# Classes.net
KiCad netlist of a schematic drawn in Altium Designer
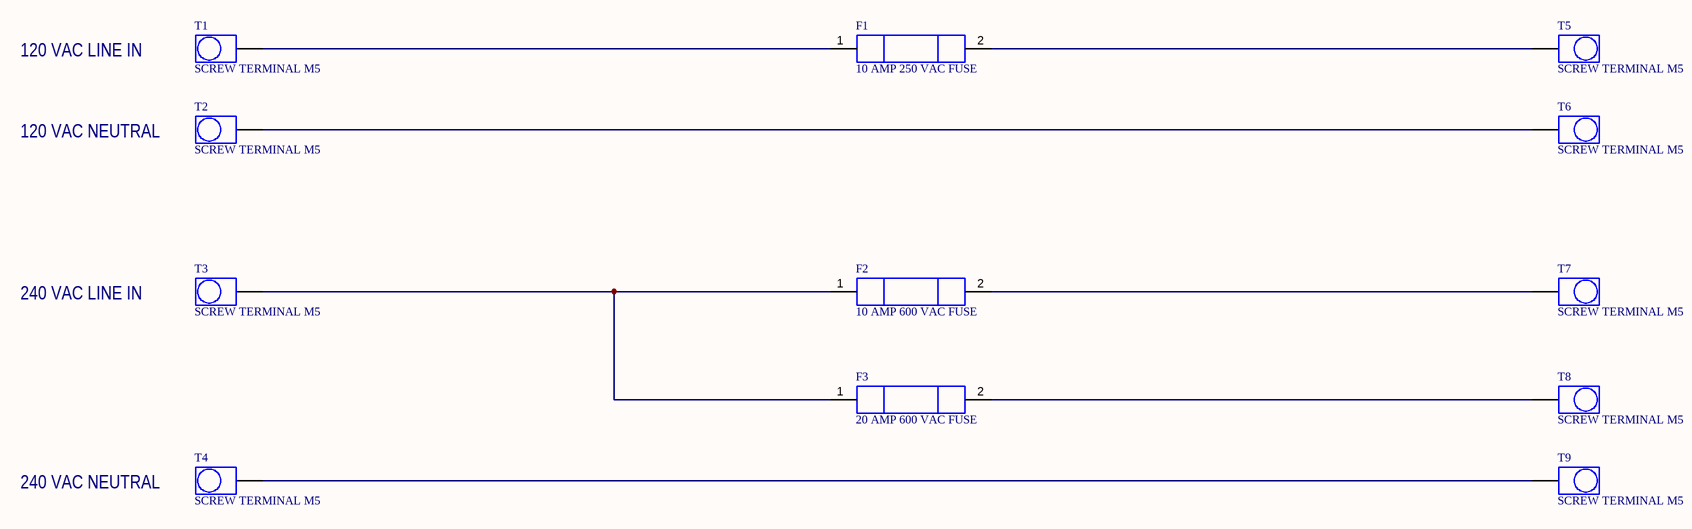
[diagram p0: Classes.SchDoc]

(export (version "E")
  (design (tool "Eeschema 10.0.6"))
  (components
    (comp (ref "F1")
      (value "10 AMP 250 VAC FUSE")
      (footprint "FUSE")
      (libsource (lib "MHH -  Altium Advanced Course A365 01") (part "Fuse3"))
    )
    (comp (ref "F2")
      (value "10 AMP 600 VAC FUSE")
      (footprint "FUSE")
      (libsource (lib "MHH -  Altium Advanced Course A365 01") (part "Fuse3"))
    )
    (comp (ref "F3")
      (value "20 AMP 600 VAC FUSE")
      (footprint "FUSE")
      (libsource (lib "MHH -  Altium Advanced Course A365 01") (part "Fuse3"))
    )
    (comp (ref "T1")
      (value "SCREW TERMINAL M5")
      (footprint "SCREW TERMINAL M5-Footprint")
      (libsource (lib "MHH -  Altium Advanced Course A365 01") (part "SCREW TERMINAL M5"))
    )
    (comp (ref "T2")
      (value "SCREW TERMINAL M5")
      (footprint "SCREW TERMINAL M5-Footprint")
      (libsource (lib "MHH -  Altium Advanced Course A365 01") (part "SCREW TERMINAL M5"))
    )
    (comp (ref "T3")
      (value "SCREW TERMINAL M5")
      (footprint "SCREW TERMINAL M5-Footprint")
      (libsource (lib "MHH -  Altium Advanced Course A365 01") (part "SCREW TERMINAL M5"))
    )
    (comp (ref "T4")
      (value "SCREW TERMINAL M5")
      (footprint "SCREW TERMINAL M5-Footprint")
      (libsource (lib "MHH -  Altium Advanced Course A365 01") (part "SCREW TERMINAL M5"))
    )
    (comp (ref "T5")
      (value "SCREW TERMINAL M5")
      (footprint "SCREW TERMINAL M5-Footprint")
      (libsource (lib "MHH -  Altium Advanced Course A365 01") (part "SCREW TERMINAL M5"))
    )
    (comp (ref "T6")
      (value "SCREW TERMINAL M5")
      (footprint "SCREW TERMINAL M5-Footprint")
      (libsource (lib "MHH -  Altium Advanced Course A365 01") (part "SCREW TERMINAL M5"))
    )
    (comp (ref "T7")
      (value "SCREW TERMINAL M5")
      (footprint "SCREW TERMINAL M5-Footprint")
      (libsource (lib "MHH -  Altium Advanced Course A365 01") (part "SCREW TERMINAL M5"))
    )
    (comp (ref "T8")
      (value "SCREW TERMINAL M5")
      (footprint "SCREW TERMINAL M5-Footprint")
      (libsource (lib "MHH -  Altium Advanced Course A365 01") (part "SCREW TERMINAL M5"))
    )
    (comp (ref "T9")
      (value "SCREW TERMINAL M5")
      (footprint "SCREW TERMINAL M5-Footprint")
      (libsource (lib "MHH -  Altium Advanced Course A365 01") (part "SCREW TERMINAL M5"))
    )
  )
  (nets
    (net (code "1") (name "Net-(F1-Pad1)") (class "Default")
      (node (ref "F1") (pin "1") (pinfunction "1_1") (pintype "passive"))
      (node (ref "T1") (pin "1") (pinfunction "1_1") (pintype "passive"))
    )
    (net (code "2") (name "Net-(F1-Pad2)") (class "Default")
      (node (ref "F1") (pin "2") (pinfunction "2_2") (pintype "passive"))
      (node (ref "T5") (pin "1") (pinfunction "1_1") (pintype "passive"))
    )
    (net (code "3") (name "Net-(F2-Pad1)") (class "Default")
      (node (ref "F2") (pin "1") (pinfunction "1_1") (pintype "passive"))
      (node (ref "F3") (pin "1") (pinfunction "1_1") (pintype "passive"))
      (node (ref "T3") (pin "1") (pinfunction "1_1") (pintype "passive"))
    )
    (net (code "4") (name "Net-(F2-Pad2)") (class "Default")
      (node (ref "F2") (pin "2") (pinfunction "2_2") (pintype "passive"))
      (node (ref "T7") (pin "1") (pinfunction "1_1") (pintype "passive"))
    )
    (net (code "5") (name "Net-(F3-Pad2)") (class "Default")
      (node (ref "F3") (pin "2") (pinfunction "2_2") (pintype "passive"))
      (node (ref "T8") (pin "1") (pinfunction "1_1") (pintype "passive"))
    )
    (net (code "6") (name "Net-(T2-Pad1)") (class "Default")
      (node (ref "T2") (pin "1") (pinfunction "1_1") (pintype "passive"))
      (node (ref "T6") (pin "1") (pinfunction "1_1") (pintype "passive"))
    )
    (net (code "7") (name "Net-(T4-Pad1)") (class "Default")
      (node (ref "T4") (pin "1") (pinfunction "1_1") (pintype "passive"))
      (node (ref "T9") (pin "1") (pinfunction "1_1") (pintype "passive"))
    )
  )
)
